# Motor2_PCIe.net
KiCad netlist of a schematic drawn in Altium Designer
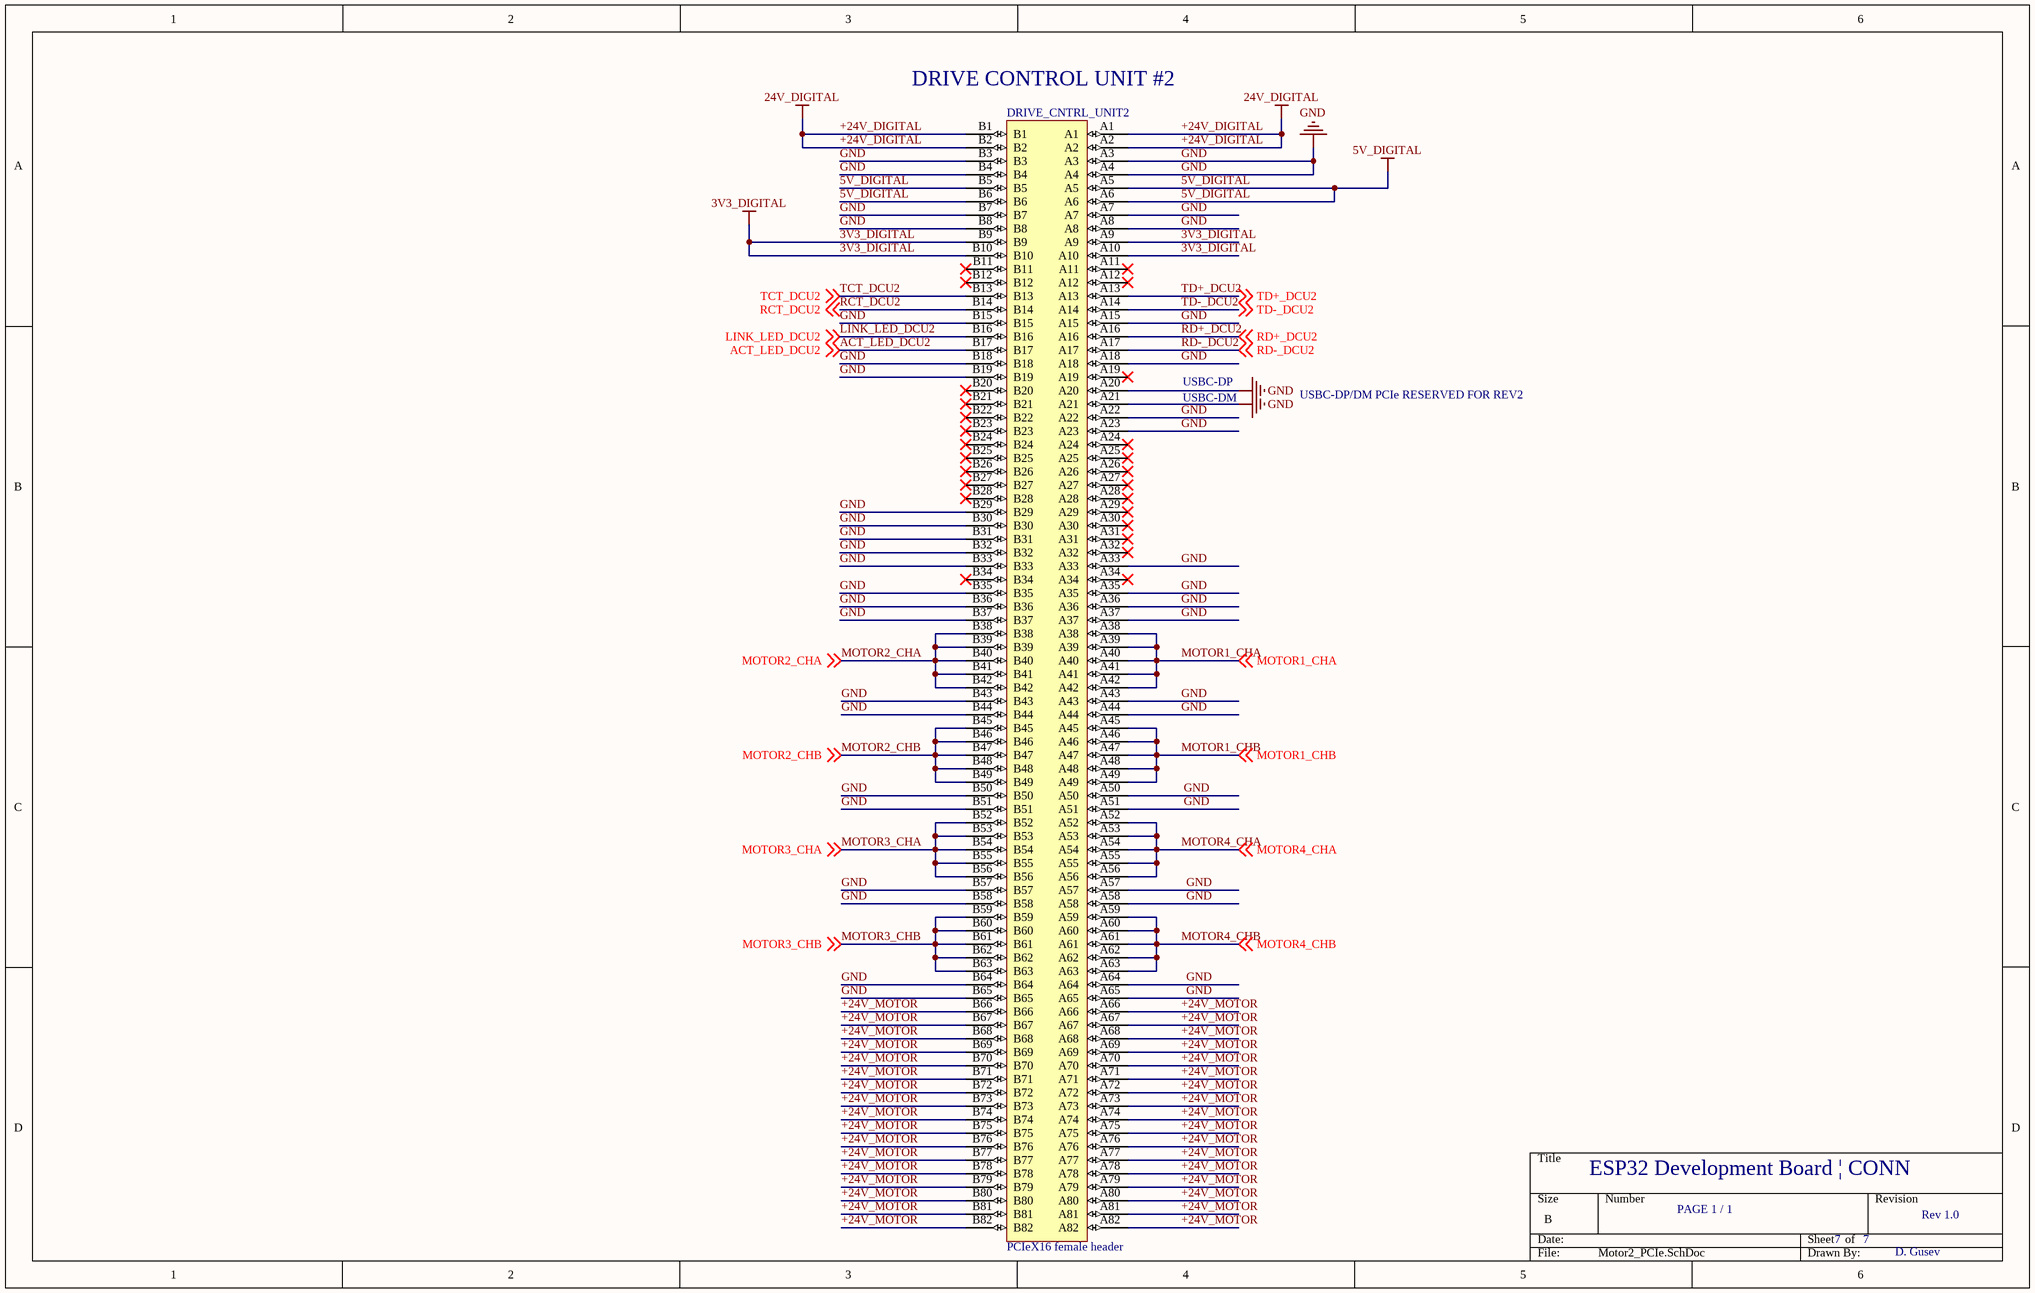
[diagram p0: Motor2_PCIe.SchDoc]

(export (version "E")
  (design (tool "Eeschema 10.0.6"))
  (components
    (comp (ref "DRIVE_CNTRL_UNIT2")
      (value "PCIeX16 female header")
      (footprint "SAMTEC_PCIE-164-02-X-D-TH")
      (description "164-position SAMTEC female header")
      (libsource (lib "ANTS-MotherBoard-B1") (part "PCIeX16 female header"))
    )
  )
  (nets
    (net (code "1") (name "/+24V_MOTOR") (class "Default")
      (node (ref "DRIVE_CNTRL_UNIT2") (pin "A66") (pinfunction "A66_A66") (pintype "bidirectional"))
      (node (ref "DRIVE_CNTRL_UNIT2") (pin "A67") (pinfunction "A67_A67") (pintype "bidirectional"))
      (node (ref "DRIVE_CNTRL_UNIT2") (pin "A68") (pinfunction "A68_A68") (pintype "bidirectional"))
      (node (ref "DRIVE_CNTRL_UNIT2") (pin "A69") (pinfunction "A69_A69") (pintype "bidirectional"))
      (node (ref "DRIVE_CNTRL_UNIT2") (pin "A70") (pinfunction "A70_A70") (pintype "bidirectional"))
      (node (ref "DRIVE_CNTRL_UNIT2") (pin "A71") (pinfunction "A71_A71") (pintype "bidirectional"))
      (node (ref "DRIVE_CNTRL_UNIT2") (pin "A72") (pinfunction "A72_A72") (pintype "bidirectional"))
      (node (ref "DRIVE_CNTRL_UNIT2") (pin "A73") (pinfunction "A73_A73") (pintype "bidirectional"))
      (node (ref "DRIVE_CNTRL_UNIT2") (pin "A74") (pinfunction "A74_A74") (pintype "bidirectional"))
      (node (ref "DRIVE_CNTRL_UNIT2") (pin "A75") (pinfunction "A75_A75") (pintype "bidirectional"))
      (node (ref "DRIVE_CNTRL_UNIT2") (pin "A76") (pinfunction "A76_A76") (pintype "bidirectional"))
      (node (ref "DRIVE_CNTRL_UNIT2") (pin "A77") (pinfunction "A77_A77") (pintype "bidirectional"))
      (node (ref "DRIVE_CNTRL_UNIT2") (pin "A78") (pinfunction "A78_A78") (pintype "bidirectional"))
      (node (ref "DRIVE_CNTRL_UNIT2") (pin "A79") (pinfunction "A79_A79") (pintype "bidirectional"))
      (node (ref "DRIVE_CNTRL_UNIT2") (pin "A80") (pinfunction "A80_A80") (pintype "bidirectional"))
      (node (ref "DRIVE_CNTRL_UNIT2") (pin "A81") (pinfunction "A81_A81") (pintype "bidirectional"))
      (node (ref "DRIVE_CNTRL_UNIT2") (pin "A82") (pinfunction "A82_A82") (pintype "bidirectional"))
      (node (ref "DRIVE_CNTRL_UNIT2") (pin "B66") (pinfunction "B66_B66") (pintype "bidirectional"))
      (node (ref "DRIVE_CNTRL_UNIT2") (pin "B67") (pinfunction "B67_B67") (pintype "bidirectional"))
      (node (ref "DRIVE_CNTRL_UNIT2") (pin "B68") (pinfunction "B68_B68") (pintype "bidirectional"))
      (node (ref "DRIVE_CNTRL_UNIT2") (pin "B69") (pinfunction "B69_B69") (pintype "bidirectional"))
      (node (ref "DRIVE_CNTRL_UNIT2") (pin "B70") (pinfunction "B70_B70") (pintype "bidirectional"))
      (node (ref "DRIVE_CNTRL_UNIT2") (pin "B71") (pinfunction "B71_B71") (pintype "bidirectional"))
      (node (ref "DRIVE_CNTRL_UNIT2") (pin "B72") (pinfunction "B72_B72") (pintype "bidirectional"))
      (node (ref "DRIVE_CNTRL_UNIT2") (pin "B73") (pinfunction "B73_B73") (pintype "bidirectional"))
      (node (ref "DRIVE_CNTRL_UNIT2") (pin "B74") (pinfunction "B74_B74") (pintype "bidirectional"))
      (node (ref "DRIVE_CNTRL_UNIT2") (pin "B75") (pinfunction "B75_B75") (pintype "bidirectional"))
      (node (ref "DRIVE_CNTRL_UNIT2") (pin "B76") (pinfunction "B76_B76") (pintype "bidirectional"))
      (node (ref "DRIVE_CNTRL_UNIT2") (pin "B77") (pinfunction "B77_B77") (pintype "bidirectional"))
      (node (ref "DRIVE_CNTRL_UNIT2") (pin "B78") (pinfunction "B78_B78") (pintype "bidirectional"))
      (node (ref "DRIVE_CNTRL_UNIT2") (pin "B79") (pinfunction "B79_B79") (pintype "bidirectional"))
      (node (ref "DRIVE_CNTRL_UNIT2") (pin "B80") (pinfunction "B80_B80") (pintype "bidirectional"))
      (node (ref "DRIVE_CNTRL_UNIT2") (pin "B81") (pinfunction "B81_B81") (pintype "bidirectional"))
      (node (ref "DRIVE_CNTRL_UNIT2") (pin "B82") (pinfunction "B82_B82") (pintype "bidirectional"))
    )
    (net (code "2") (name "3V3_DIGITAL") (class "Default")
      (node (ref "DRIVE_CNTRL_UNIT2") (pin "A10") (pinfunction "A10_A10") (pintype "bidirectional"))
      (node (ref "DRIVE_CNTRL_UNIT2") (pin "A9") (pinfunction "A9_A9") (pintype "bidirectional"))
      (node (ref "DRIVE_CNTRL_UNIT2") (pin "B10") (pinfunction "B10_B10") (pintype "bidirectional"))
      (node (ref "DRIVE_CNTRL_UNIT2") (pin "B9") (pinfunction "B9_B9") (pintype "bidirectional"))
    )
    (net (code "3") (name "5V_DIGITAL") (class "Default")
      (node (ref "DRIVE_CNTRL_UNIT2") (pin "A5") (pinfunction "A5_A5") (pintype "bidirectional"))
      (node (ref "DRIVE_CNTRL_UNIT2") (pin "A6") (pinfunction "A6_A6") (pintype "bidirectional"))
      (node (ref "DRIVE_CNTRL_UNIT2") (pin "B5") (pinfunction "B5_B5") (pintype "bidirectional"))
      (node (ref "DRIVE_CNTRL_UNIT2") (pin "B6") (pinfunction "B6_B6") (pintype "bidirectional"))
    )
    (net (code "4") (name "24V_DIGITAL") (class "Default")
      (node (ref "DRIVE_CNTRL_UNIT2") (pin "A1") (pinfunction "A1_A1") (pintype "bidirectional"))
      (node (ref "DRIVE_CNTRL_UNIT2") (pin "A2") (pinfunction "A2_A2") (pintype "bidirectional"))
      (node (ref "DRIVE_CNTRL_UNIT2") (pin "B1") (pinfunction "B1_B1") (pintype "bidirectional"))
      (node (ref "DRIVE_CNTRL_UNIT2") (pin "B2") (pinfunction "B2_B2") (pintype "bidirectional"))
    )
    (net (code "5") (name "ACT_LED_DCU2") (class "Default")
      (node (ref "DRIVE_CNTRL_UNIT2") (pin "B17") (pinfunction "B17_B17") (pintype "bidirectional"))
    )
    (net (code "6") (name "GND") (class "Default")
      (node (ref "DRIVE_CNTRL_UNIT2") (pin "A15") (pinfunction "A15_A15") (pintype "bidirectional"))
      (node (ref "DRIVE_CNTRL_UNIT2") (pin "A18") (pinfunction "A18_A18") (pintype "bidirectional"))
      (node (ref "DRIVE_CNTRL_UNIT2") (pin "A20") (pinfunction "A20_A20") (pintype "bidirectional"))
      (node (ref "DRIVE_CNTRL_UNIT2") (pin "A21") (pinfunction "A21_A21") (pintype "bidirectional"))
      (node (ref "DRIVE_CNTRL_UNIT2") (pin "A22") (pinfunction "A22_A22") (pintype "bidirectional"))
      (node (ref "DRIVE_CNTRL_UNIT2") (pin "A23") (pinfunction "A23_A23") (pintype "bidirectional"))
      (node (ref "DRIVE_CNTRL_UNIT2") (pin "A3") (pinfunction "A3_A3") (pintype "bidirectional"))
      (node (ref "DRIVE_CNTRL_UNIT2") (pin "A33") (pinfunction "A33_A33") (pintype "bidirectional"))
      (node (ref "DRIVE_CNTRL_UNIT2") (pin "A35") (pinfunction "A35_A35") (pintype "bidirectional"))
      (node (ref "DRIVE_CNTRL_UNIT2") (pin "A36") (pinfunction "A36_A36") (pintype "bidirectional"))
      (node (ref "DRIVE_CNTRL_UNIT2") (pin "A37") (pinfunction "A37_A37") (pintype "bidirectional"))
      (node (ref "DRIVE_CNTRL_UNIT2") (pin "A4") (pinfunction "A4_A4") (pintype "bidirectional"))
      (node (ref "DRIVE_CNTRL_UNIT2") (pin "A43") (pinfunction "A43_A43") (pintype "bidirectional"))
      (node (ref "DRIVE_CNTRL_UNIT2") (pin "A44") (pinfunction "A44_A44") (pintype "bidirectional"))
      (node (ref "DRIVE_CNTRL_UNIT2") (pin "A50") (pinfunction "A50_A50") (pintype "bidirectional"))
      (node (ref "DRIVE_CNTRL_UNIT2") (pin "A51") (pinfunction "A51_A51") (pintype "bidirectional"))
      (node (ref "DRIVE_CNTRL_UNIT2") (pin "A57") (pinfunction "A57_A57") (pintype "bidirectional"))
      (node (ref "DRIVE_CNTRL_UNIT2") (pin "A58") (pinfunction "A58_A58") (pintype "bidirectional"))
      (node (ref "DRIVE_CNTRL_UNIT2") (pin "A64") (pinfunction "A64_A64") (pintype "bidirectional"))
      (node (ref "DRIVE_CNTRL_UNIT2") (pin "A65") (pinfunction "A65_A65") (pintype "bidirectional"))
      (node (ref "DRIVE_CNTRL_UNIT2") (pin "A7") (pinfunction "A7_A7") (pintype "bidirectional"))
      (node (ref "DRIVE_CNTRL_UNIT2") (pin "A8") (pinfunction "A8_A8") (pintype "bidirectional"))
      (node (ref "DRIVE_CNTRL_UNIT2") (pin "B15") (pinfunction "B15_B15") (pintype "bidirectional"))
      (node (ref "DRIVE_CNTRL_UNIT2") (pin "B18") (pinfunction "B18_B18") (pintype "bidirectional"))
      (node (ref "DRIVE_CNTRL_UNIT2") (pin "B19") (pinfunction "B19_B19") (pintype "bidirectional"))
      (node (ref "DRIVE_CNTRL_UNIT2") (pin "B29") (pinfunction "B29_B29") (pintype "bidirectional"))
      (node (ref "DRIVE_CNTRL_UNIT2") (pin "B3") (pinfunction "B3_B3") (pintype "bidirectional"))
      (node (ref "DRIVE_CNTRL_UNIT2") (pin "B30") (pinfunction "B30_B30") (pintype "bidirectional"))
      (node (ref "DRIVE_CNTRL_UNIT2") (pin "B31") (pinfunction "B31_B31") (pintype "bidirectional"))
      (node (ref "DRIVE_CNTRL_UNIT2") (pin "B32") (pinfunction "B32_B32") (pintype "bidirectional"))
      (node (ref "DRIVE_CNTRL_UNIT2") (pin "B33") (pinfunction "B33_B33") (pintype "bidirectional"))
      (node (ref "DRIVE_CNTRL_UNIT2") (pin "B35") (pinfunction "B35_B35") (pintype "bidirectional"))
      (node (ref "DRIVE_CNTRL_UNIT2") (pin "B36") (pinfunction "B36_B36") (pintype "bidirectional"))
      (node (ref "DRIVE_CNTRL_UNIT2") (pin "B37") (pinfunction "B37_B37") (pintype "bidirectional"))
      (node (ref "DRIVE_CNTRL_UNIT2") (pin "B4") (pinfunction "B4_B4") (pintype "bidirectional"))
      (node (ref "DRIVE_CNTRL_UNIT2") (pin "B43") (pinfunction "B43_B43") (pintype "bidirectional"))
      (node (ref "DRIVE_CNTRL_UNIT2") (pin "B44") (pinfunction "B44_B44") (pintype "bidirectional"))
      (node (ref "DRIVE_CNTRL_UNIT2") (pin "B50") (pinfunction "B50_B50") (pintype "bidirectional"))
      (node (ref "DRIVE_CNTRL_UNIT2") (pin "B51") (pinfunction "B51_B51") (pintype "bidirectional"))
      (node (ref "DRIVE_CNTRL_UNIT2") (pin "B57") (pinfunction "B57_B57") (pintype "bidirectional"))
      (node (ref "DRIVE_CNTRL_UNIT2") (pin "B58") (pinfunction "B58_B58") (pintype "bidirectional"))
      (node (ref "DRIVE_CNTRL_UNIT2") (pin "B64") (pinfunction "B64_B64") (pintype "bidirectional"))
      (node (ref "DRIVE_CNTRL_UNIT2") (pin "B65") (pinfunction "B65_B65") (pintype "bidirectional"))
      (node (ref "DRIVE_CNTRL_UNIT2") (pin "B7") (pinfunction "B7_B7") (pintype "bidirectional"))
      (node (ref "DRIVE_CNTRL_UNIT2") (pin "B8") (pinfunction "B8_B8") (pintype "bidirectional"))
    )
    (net (code "7") (name "LINK_LED_DCU2") (class "Default")
      (node (ref "DRIVE_CNTRL_UNIT2") (pin "B16") (pinfunction "B16_B16") (pintype "bidirectional"))
    )
    (net (code "8") (name "MOTOR1_CHA") (class "Default")
      (node (ref "DRIVE_CNTRL_UNIT2") (pin "A38") (pinfunction "A38_A38") (pintype "bidirectional"))
      (node (ref "DRIVE_CNTRL_UNIT2") (pin "A39") (pinfunction "A39_A39") (pintype "bidirectional"))
      (node (ref "DRIVE_CNTRL_UNIT2") (pin "A40") (pinfunction "A40_A40") (pintype "bidirectional"))
      (node (ref "DRIVE_CNTRL_UNIT2") (pin "A41") (pinfunction "A41_A41") (pintype "bidirectional"))
      (node (ref "DRIVE_CNTRL_UNIT2") (pin "A42") (pinfunction "A42_A42") (pintype "bidirectional"))
    )
    (net (code "9") (name "MOTOR1_CHB") (class "Default")
      (node (ref "DRIVE_CNTRL_UNIT2") (pin "A45") (pinfunction "A45_A45") (pintype "bidirectional"))
      (node (ref "DRIVE_CNTRL_UNIT2") (pin "A46") (pinfunction "A46_A46") (pintype "bidirectional"))
      (node (ref "DRIVE_CNTRL_UNIT2") (pin "A47") (pinfunction "A47_A47") (pintype "bidirectional"))
      (node (ref "DRIVE_CNTRL_UNIT2") (pin "A48") (pinfunction "A48_A48") (pintype "bidirectional"))
      (node (ref "DRIVE_CNTRL_UNIT2") (pin "A49") (pinfunction "A49_A49") (pintype "bidirectional"))
    )
    (net (code "10") (name "MOTOR2_CHA") (class "Default")
      (node (ref "DRIVE_CNTRL_UNIT2") (pin "B38") (pinfunction "B38_B38") (pintype "bidirectional"))
      (node (ref "DRIVE_CNTRL_UNIT2") (pin "B39") (pinfunction "B39_B39") (pintype "bidirectional"))
      (node (ref "DRIVE_CNTRL_UNIT2") (pin "B40") (pinfunction "B40_B40") (pintype "bidirectional"))
      (node (ref "DRIVE_CNTRL_UNIT2") (pin "B41") (pinfunction "B41_B41") (pintype "bidirectional"))
      (node (ref "DRIVE_CNTRL_UNIT2") (pin "B42") (pinfunction "B42_B42") (pintype "bidirectional"))
    )
    (net (code "11") (name "MOTOR2_CHB") (class "Default")
      (node (ref "DRIVE_CNTRL_UNIT2") (pin "B45") (pinfunction "B45_B45") (pintype "bidirectional"))
      (node (ref "DRIVE_CNTRL_UNIT2") (pin "B46") (pinfunction "B46_B46") (pintype "bidirectional"))
      (node (ref "DRIVE_CNTRL_UNIT2") (pin "B47") (pinfunction "B47_B47") (pintype "bidirectional"))
      (node (ref "DRIVE_CNTRL_UNIT2") (pin "B48") (pinfunction "B48_B48") (pintype "bidirectional"))
      (node (ref "DRIVE_CNTRL_UNIT2") (pin "B49") (pinfunction "B49_B49") (pintype "bidirectional"))
    )
    (net (code "12") (name "MOTOR3_CHA") (class "Default")
      (node (ref "DRIVE_CNTRL_UNIT2") (pin "B52") (pinfunction "B52_B52") (pintype "bidirectional"))
      (node (ref "DRIVE_CNTRL_UNIT2") (pin "B53") (pinfunction "B53_B53") (pintype "bidirectional"))
      (node (ref "DRIVE_CNTRL_UNIT2") (pin "B54") (pinfunction "B54_B54") (pintype "bidirectional"))
      (node (ref "DRIVE_CNTRL_UNIT2") (pin "B55") (pinfunction "B55_B55") (pintype "bidirectional"))
      (node (ref "DRIVE_CNTRL_UNIT2") (pin "B56") (pinfunction "B56_B56") (pintype "bidirectional"))
    )
    (net (code "13") (name "MOTOR3_CHB") (class "Default")
      (node (ref "DRIVE_CNTRL_UNIT2") (pin "B59") (pinfunction "B59_B59") (pintype "bidirectional"))
      (node (ref "DRIVE_CNTRL_UNIT2") (pin "B60") (pinfunction "B60_B60") (pintype "bidirectional"))
      (node (ref "DRIVE_CNTRL_UNIT2") (pin "B61") (pinfunction "B61_B61") (pintype "bidirectional"))
      (node (ref "DRIVE_CNTRL_UNIT2") (pin "B62") (pinfunction "B62_B62") (pintype "bidirectional"))
      (node (ref "DRIVE_CNTRL_UNIT2") (pin "B63") (pinfunction "B63_B63") (pintype "bidirectional"))
    )
    (net (code "14") (name "MOTOR4_CHA") (class "Default")
      (node (ref "DRIVE_CNTRL_UNIT2") (pin "A52") (pinfunction "A52_A52") (pintype "bidirectional"))
      (node (ref "DRIVE_CNTRL_UNIT2") (pin "A53") (pinfunction "A53_A53") (pintype "bidirectional"))
      (node (ref "DRIVE_CNTRL_UNIT2") (pin "A54") (pinfunction "A54_A54") (pintype "bidirectional"))
      (node (ref "DRIVE_CNTRL_UNIT2") (pin "A55") (pinfunction "A55_A55") (pintype "bidirectional"))
      (node (ref "DRIVE_CNTRL_UNIT2") (pin "A56") (pinfunction "A56_A56") (pintype "bidirectional"))
    )
    (net (code "15") (name "MOTOR4_CHB") (class "Default")
      (node (ref "DRIVE_CNTRL_UNIT2") (pin "A59") (pinfunction "A59_A59") (pintype "bidirectional"))
      (node (ref "DRIVE_CNTRL_UNIT2") (pin "A60") (pinfunction "A60_A60") (pintype "bidirectional"))
      (node (ref "DRIVE_CNTRL_UNIT2") (pin "A61") (pinfunction "A61_A61") (pintype "bidirectional"))
      (node (ref "DRIVE_CNTRL_UNIT2") (pin "A62") (pinfunction "A62_A62") (pintype "bidirectional"))
      (node (ref "DRIVE_CNTRL_UNIT2") (pin "A63") (pinfunction "A63_A63") (pintype "bidirectional"))
    )
    (net (code "16") (name "RCT_DCU2") (class "Default")
      (node (ref "DRIVE_CNTRL_UNIT2") (pin "B14") (pinfunction "B14_B14") (pintype "bidirectional"))
    )
    (net (code "17") (name "RD+_DCU2") (class "Default")
      (node (ref "DRIVE_CNTRL_UNIT2") (pin "A16") (pinfunction "A16_A16") (pintype "bidirectional"))
    )
    (net (code "18") (name "RD-_DCU2") (class "Default")
      (node (ref "DRIVE_CNTRL_UNIT2") (pin "A17") (pinfunction "A17_A17") (pintype "bidirectional"))
    )
    (net (code "19") (name "TCT_DCU2") (class "Default")
      (node (ref "DRIVE_CNTRL_UNIT2") (pin "B13") (pinfunction "B13_B13") (pintype "bidirectional"))
    )
    (net (code "20") (name "TD+_DCU2") (class "Default")
      (node (ref "DRIVE_CNTRL_UNIT2") (pin "A13") (pinfunction "A13_A13") (pintype "bidirectional"))
    )
    (net (code "21") (name "TD-_DCU2") (class "Default")
      (node (ref "DRIVE_CNTRL_UNIT2") (pin "A14") (pinfunction "A14_A14") (pintype "bidirectional"))
    )
    (net (code "22") (name "unconnected-(DRIVE_CNTRL_UNIT2-PadA11)") (class "Default")
      (node (ref "DRIVE_CNTRL_UNIT2") (pin "A11") (pinfunction "A11_A11") (pintype "bidirectional+no_connect"))
    )
    (net (code "23") (name "unconnected-(DRIVE_CNTRL_UNIT2-PadA12)") (class "Default")
      (node (ref "DRIVE_CNTRL_UNIT2") (pin "A12") (pinfunction "A12_A12") (pintype "bidirectional+no_connect"))
    )
    (net (code "24") (name "unconnected-(DRIVE_CNTRL_UNIT2-PadA19)") (class "Default")
      (node (ref "DRIVE_CNTRL_UNIT2") (pin "A19") (pinfunction "A19_A19") (pintype "bidirectional+no_connect"))
    )
    (net (code "25") (name "unconnected-(DRIVE_CNTRL_UNIT2-PadA24)") (class "Default")
      (node (ref "DRIVE_CNTRL_UNIT2") (pin "A24") (pinfunction "A24_A24") (pintype "bidirectional+no_connect"))
    )
    (net (code "26") (name "unconnected-(DRIVE_CNTRL_UNIT2-PadA25)") (class "Default")
      (node (ref "DRIVE_CNTRL_UNIT2") (pin "A25") (pinfunction "A25_A25") (pintype "bidirectional+no_connect"))
    )
    (net (code "27") (name "unconnected-(DRIVE_CNTRL_UNIT2-PadA26)") (class "Default")
      (node (ref "DRIVE_CNTRL_UNIT2") (pin "A26") (pinfunction "A26_A26") (pintype "bidirectional+no_connect"))
    )
    (net (code "28") (name "unconnected-(DRIVE_CNTRL_UNIT2-PadA27)") (class "Default")
      (node (ref "DRIVE_CNTRL_UNIT2") (pin "A27") (pinfunction "A27_A27") (pintype "bidirectional+no_connect"))
    )
    (net (code "29") (name "unconnected-(DRIVE_CNTRL_UNIT2-PadA28)") (class "Default")
      (node (ref "DRIVE_CNTRL_UNIT2") (pin "A28") (pinfunction "A28_A28") (pintype "bidirectional+no_connect"))
    )
    (net (code "30") (name "unconnected-(DRIVE_CNTRL_UNIT2-PadA29)") (class "Default")
      (node (ref "DRIVE_CNTRL_UNIT2") (pin "A29") (pinfunction "A29_A29") (pintype "bidirectional+no_connect"))
    )
    (net (code "31") (name "unconnected-(DRIVE_CNTRL_UNIT2-PadA30)") (class "Default")
      (node (ref "DRIVE_CNTRL_UNIT2") (pin "A30") (pinfunction "A30_A30") (pintype "bidirectional+no_connect"))
    )
    (net (code "32") (name "unconnected-(DRIVE_CNTRL_UNIT2-PadA31)") (class "Default")
      (node (ref "DRIVE_CNTRL_UNIT2") (pin "A31") (pinfunction "A31_A31") (pintype "bidirectional+no_connect"))
    )
    (net (code "33") (name "unconnected-(DRIVE_CNTRL_UNIT2-PadA32)") (class "Default")
      (node (ref "DRIVE_CNTRL_UNIT2") (pin "A32") (pinfunction "A32_A32") (pintype "bidirectional+no_connect"))
    )
    (net (code "34") (name "unconnected-(DRIVE_CNTRL_UNIT2-PadA34)") (class "Default")
      (node (ref "DRIVE_CNTRL_UNIT2") (pin "A34") (pinfunction "A34_A34") (pintype "bidirectional+no_connect"))
    )
    (net (code "35") (name "unconnected-(DRIVE_CNTRL_UNIT2-PadB11)") (class "Default")
      (node (ref "DRIVE_CNTRL_UNIT2") (pin "B11") (pinfunction "B11_B11") (pintype "bidirectional+no_connect"))
    )
    (net (code "36") (name "unconnected-(DRIVE_CNTRL_UNIT2-PadB12)") (class "Default")
      (node (ref "DRIVE_CNTRL_UNIT2") (pin "B12") (pinfunction "B12_B12") (pintype "bidirectional+no_connect"))
    )
    (net (code "37") (name "unconnected-(DRIVE_CNTRL_UNIT2-PadB20)") (class "Default")
      (node (ref "DRIVE_CNTRL_UNIT2") (pin "B20") (pinfunction "B20_B20") (pintype "bidirectional+no_connect"))
    )
    (net (code "38") (name "unconnected-(DRIVE_CNTRL_UNIT2-PadB21)") (class "Default")
      (node (ref "DRIVE_CNTRL_UNIT2") (pin "B21") (pinfunction "B21_B21") (pintype "bidirectional+no_connect"))
    )
    (net (code "39") (name "unconnected-(DRIVE_CNTRL_UNIT2-PadB22)") (class "Default")
      (node (ref "DRIVE_CNTRL_UNIT2") (pin "B22") (pinfunction "B22_B22") (pintype "bidirectional+no_connect"))
    )
    (net (code "40") (name "unconnected-(DRIVE_CNTRL_UNIT2-PadB23)") (class "Default")
      (node (ref "DRIVE_CNTRL_UNIT2") (pin "B23") (pinfunction "B23_B23") (pintype "bidirectional+no_connect"))
    )
    (net (code "41") (name "unconnected-(DRIVE_CNTRL_UNIT2-PadB24)") (class "Default")
      (node (ref "DRIVE_CNTRL_UNIT2") (pin "B24") (pinfunction "B24_B24") (pintype "bidirectional+no_connect"))
    )
    (net (code "42") (name "unconnected-(DRIVE_CNTRL_UNIT2-PadB25)") (class "Default")
      (node (ref "DRIVE_CNTRL_UNIT2") (pin "B25") (pinfunction "B25_B25") (pintype "bidirectional+no_connect"))
    )
    (net (code "43") (name "unconnected-(DRIVE_CNTRL_UNIT2-PadB26)") (class "Default")
      (node (ref "DRIVE_CNTRL_UNIT2") (pin "B26") (pinfunction "B26_B26") (pintype "bidirectional+no_connect"))
    )
    (net (code "44") (name "unconnected-(DRIVE_CNTRL_UNIT2-PadB27)") (class "Default")
      (node (ref "DRIVE_CNTRL_UNIT2") (pin "B27") (pinfunction "B27_B27") (pintype "bidirectional+no_connect"))
    )
    (net (code "45") (name "unconnected-(DRIVE_CNTRL_UNIT2-PadB28)") (class "Default")
      (node (ref "DRIVE_CNTRL_UNIT2") (pin "B28") (pinfunction "B28_B28") (pintype "bidirectional+no_connect"))
    )
    (net (code "46") (name "unconnected-(DRIVE_CNTRL_UNIT2-PadB34)") (class "Default")
      (node (ref "DRIVE_CNTRL_UNIT2") (pin "B34") (pinfunction "B34_B34") (pintype "bidirectional+no_connect"))
    )
  )
)
